# TinyMicroGameboy-smallbuttons.net
KiCad netlist of a schematic drawn in EAGLE
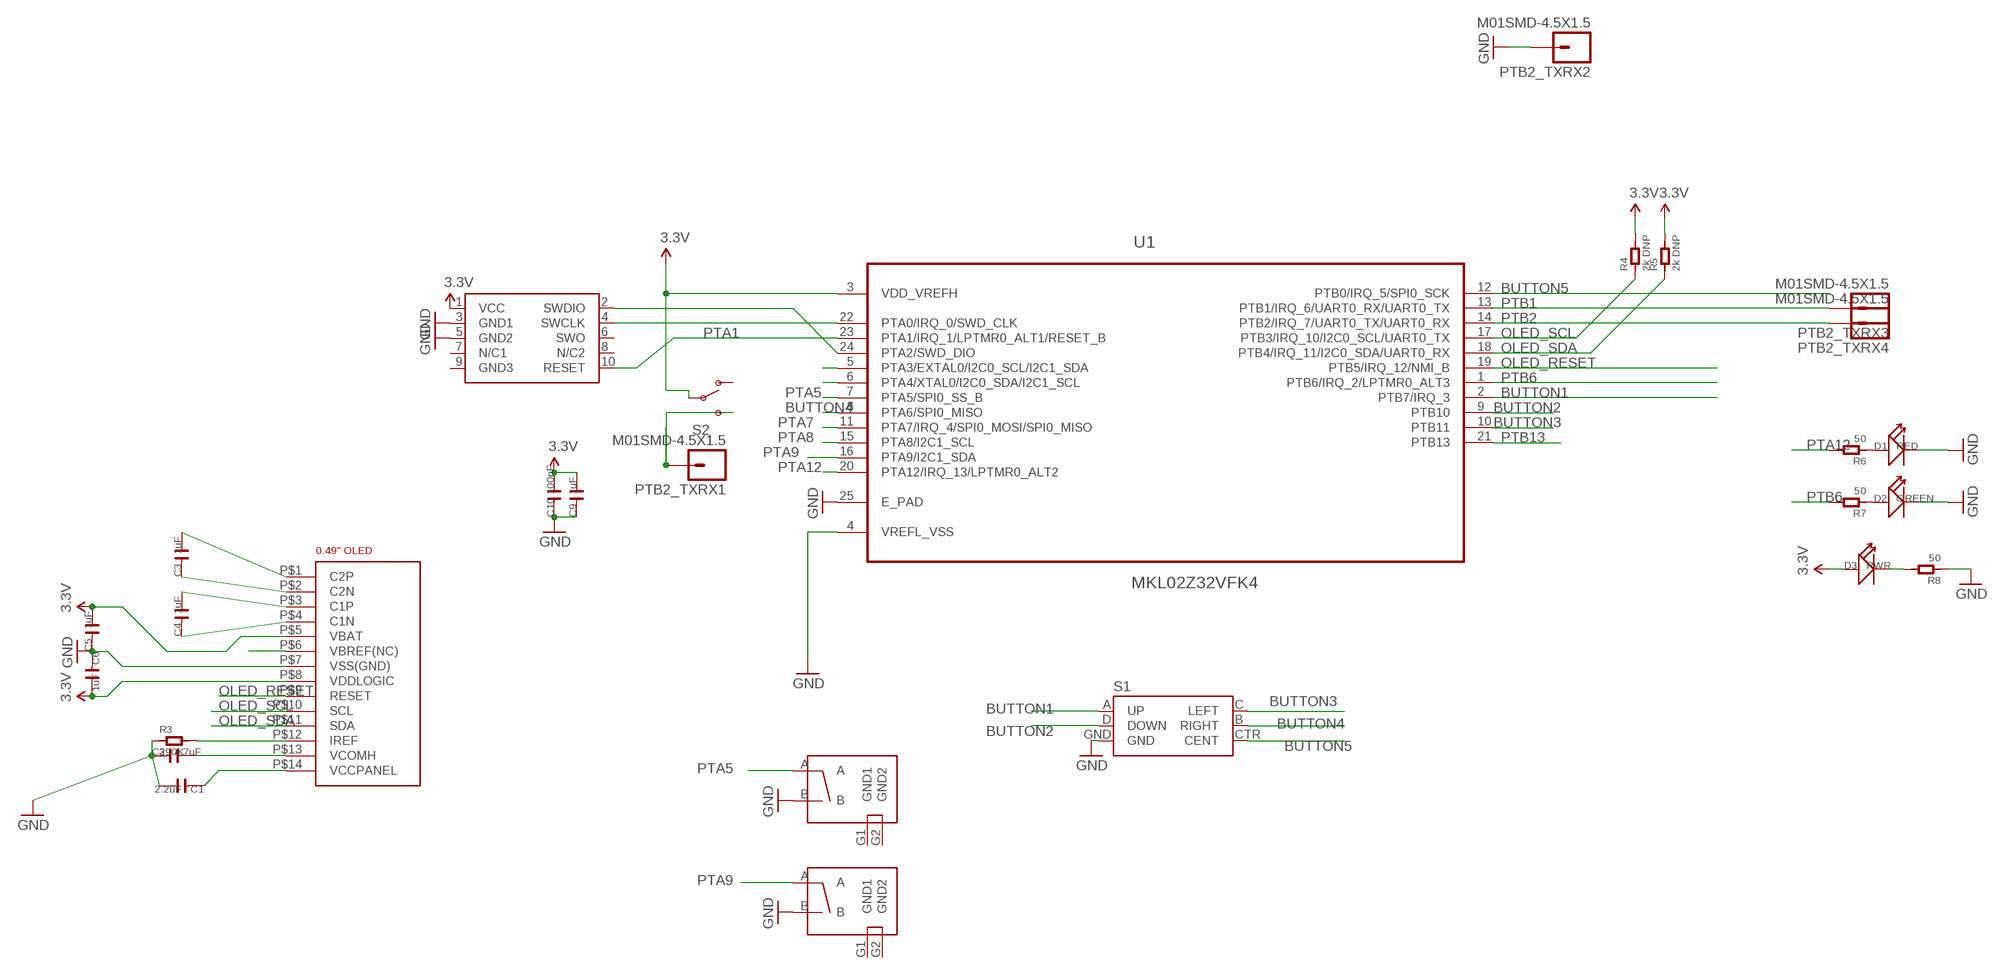
[diagram p0: schematic, sheet 1]

(export (version "E")
  (design (tool "Eeschema 10.0.6"))
  (components
    (comp (ref "C1")
      (value "2.2uF")
      (footprint "eagle-import:C0603")
      (libsource (lib "eagle-import") (part "C-0603"))
    )
    (comp (ref "C2")
      (value "4.7uF")
      (footprint "eagle-import:C0603")
      (libsource (lib "eagle-import") (part "C-0603"))
    )
    (comp (ref "C3")
      (value "1uF")
      (footprint "eagle-import:C0603")
      (libsource (lib "eagle-import") (part "C-0603"))
    )
    (comp (ref "C4")
      (value "1uF")
      (footprint "eagle-import:C0603")
      (libsource (lib "eagle-import") (part "C-0603"))
    )
    (comp (ref "C5")
      (value "1uF")
      (footprint "eagle-import:C0603")
      (libsource (lib "eagle-import") (part "C-0603"))
    )
    (comp (ref "C6")
      (value "1uF")
      (footprint "eagle-import:C0603")
      (libsource (lib "eagle-import") (part "C-0603"))
    )
    (comp (ref "C9")
      (value "1uF")
      (footprint "eagle-import:C0603")
      (libsource (lib "eagle-import") (part "C-0603"))
    )
    (comp (ref "C10")
      (value "100nF")
      (footprint "eagle-import:C0603")
      (libsource (lib "eagle-import") (part "C-0603"))
    )
    (comp (ref "D1")
      (value "RED")
      (footprint "eagle-import:LED0603")
      (libsource (lib "eagle-import") (part "LED"))
    )
    (comp (ref "D2")
      (value "GREEN")
      (footprint "eagle-import:LED0603")
      (libsource (lib "eagle-import") (part "LED"))
    )
    (comp (ref "D3")
      (value "PWR")
      (footprint "eagle-import:LED0603")
      (libsource (lib "eagle-import") (part "LED"))
    )
    (comp (ref "PTB2_TXRX1")
      (value "M01SMD-4.5X1.5")
      (footprint "eagle-import:PAD-1.5X4.5")
      (libsource (lib "eagle-import") (part "M01SMD-4.5X1.5"))
    )
    (comp (ref "PTB2_TXRX2")
      (value "M01SMD-4.5X1.5")
      (footprint "eagle-import:PAD-1.5X4.5")
      (libsource (lib "eagle-import") (part "M01SMD-4.5X1.5"))
    )
    (comp (ref "PTB2_TXRX3")
      (value "M01SMD-4.5X1.5")
      (footprint "eagle-import:PAD-1.5X4.5")
      (libsource (lib "eagle-import") (part "M01SMD-4.5X1.5"))
    )
    (comp (ref "PTB2_TXRX4")
      (value "M01SMD-4.5X1.5")
      (footprint "eagle-import:PAD-1.5X4.5")
      (libsource (lib "eagle-import") (part "M01SMD-4.5X1.5"))
    )
    (comp (ref "R3")
      (value "390K")
      (footprint "eagle-import:R0603")
      (libsource (lib "eagle-import") (part "R-0603"))
    )
    (comp (ref "R4")
      (value "2k DNP")
      (footprint "eagle-import:R0603")
      (libsource (lib "eagle-import") (part "R-0603"))
    )
    (comp (ref "R5")
      (value "2k DNP")
      (footprint "eagle-import:R0603")
      (libsource (lib "eagle-import") (part "R-0603"))
    )
    (comp (ref "R6")
      (value "50")
      (footprint "eagle-import:R0603")
      (libsource (lib "eagle-import") (part "R-0603"))
    )
    (comp (ref "R7")
      (value "50")
      (footprint "eagle-import:R0603")
      (libsource (lib "eagle-import") (part "R-0603"))
    )
    (comp (ref "R8")
      (value "50")
      (footprint "eagle-import:R0603")
      (libsource (lib "eagle-import") (part "R-0603"))
    )
    (comp (ref "S1")
      (value "JOYSTICK_MINI")
      (footprint "eagle-import:JOYSTICK_MINI")
      (libsource (lib "eagle-import") (part "JOYSTICK_MINI"))
    )
    (comp (ref "S2")
      (value "SWITCH-SPDT-SMD-A")
      (footprint "eagle-import:SWITCH-SPST-SMD-A")
      (libsource (lib "eagle-import") (part "SWITCH-SPDT-SMD-A"))
    )
    (comp (ref "SWD1")
      (value "CORTEX_SWD")
      (footprint "eagle-import:M50-3600542")
      (libsource (lib "eagle-import") (part "CORTEX_SWD"))
    )
    (comp (ref "U$1")
      (value "0.49\"OLEDFOLDED")
      (footprint "eagle-import:0.49_-FPC-0.7-14-FOLDED")
      (libsource (lib "eagle-import") (part "0.49{dblquote}OLEDFOLDED"))
    )
    (comp (ref "U$2")
      (value "2PSWITCH_SMT_SIDEMOUNT")
      (footprint "eagle-import:2X4TACT")
      (libsource (lib "eagle-import") (part "2PSWITCH_SMT_SIDEMOUNT"))
    )
    (comp (ref "U$3")
      (value "2PSWITCH_SMT_SIDEMOUNT")
      (footprint "eagle-import:2X4TACT")
      (libsource (lib "eagle-import") (part "2PSWITCH_SMT_SIDEMOUNT"))
    )
    (comp (ref "U1")
      (value "MKL02Z32VFK4")
      (footprint "eagle-import:QFN50P400X400X100-25N")
      (libsource (lib "eagle-import") (part "MKL02Z32VFK4"))
    )
  )
  (nets
    (net (code "1") (name "/BUTTON1") (class "Default")
      (node (ref "S1") (pin "A") (pinfunction "UP_A") (pintype "bidirectional"))
      (node (ref "U1") (pin "2") (pinfunction "PTB7/IRQ_3_2") (pintype "bidirectional"))
    )
    (net (code "2") (name "/BUTTON2") (class "Default")
      (node (ref "S1") (pin "D") (pinfunction "DOWN_D") (pintype "bidirectional"))
      (node (ref "U1") (pin "9") (pinfunction "PTB10_9") (pintype "bidirectional"))
    )
    (net (code "3") (name "/BUTTON3") (class "Default")
      (node (ref "S1") (pin "C") (pinfunction "LEFT_C") (pintype "bidirectional"))
      (node (ref "U1") (pin "10") (pinfunction "PTB11_10") (pintype "bidirectional"))
    )
    (net (code "4") (name "/BUTTON4") (class "Default")
      (node (ref "S1") (pin "B") (pinfunction "RIGHT_B") (pintype "bidirectional"))
      (node (ref "U1") (pin "8") (pinfunction "PTA6/SPI0_MISO_8") (pintype "bidirectional"))
    )
    (net (code "5") (name "/BUTTON5") (class "Default")
      (node (ref "S1") (pin "CTR") (pinfunction "CENT_CTR") (pintype "bidirectional"))
      (node (ref "U1") (pin "12") (pinfunction "PTB0/IRQ_5/SPI0_SCK_12") (pintype "bidirectional"))
    )
    (net (code "6") (name "/OLED_RESET") (class "Default")
      (node (ref "U$1") (pin "P$9") (pinfunction "RESET_P$9") (pintype "bidirectional"))
      (node (ref "U1") (pin "19") (pinfunction "PTB5/IRQ_12/NMI_B_19") (pintype "bidirectional"))
    )
    (net (code "7") (name "/OLED_SCL") (class "Default")
      (node (ref "R4") (pin "1") (pinfunction "1_1") (pintype "bidirectional"))
      (node (ref "U$1") (pin "P$10") (pinfunction "SCL_P$10") (pintype "bidirectional"))
      (node (ref "U1") (pin "17") (pinfunction "PTB3/IRQ_10/I2C0_SCL/UART0_TX_17") (pintype "bidirectional"))
    )
    (net (code "8") (name "/OLED_SDA") (class "Default")
      (node (ref "R5") (pin "1") (pinfunction "1_1") (pintype "bidirectional"))
      (node (ref "U$1") (pin "P$11") (pinfunction "SDA_P$11") (pintype "bidirectional"))
      (node (ref "U1") (pin "18") (pinfunction "PTB4/IRQ_11/I2C0_SDA/UART0_RX_18") (pintype "bidirectional"))
    )
    (net (code "9") (name "/PTA1") (class "Default")
      (node (ref "SWD1") (pin "10") (pinfunction "RESET_10") (pintype "bidirectional"))
      (node (ref "U1") (pin "23") (pinfunction "PTA1/IRQ_1/LPTMR0_ALT1/RESET_B_23") (pintype "bidirectional"))
    )
    (net (code "10") (name "/PTA5") (class "Default")
      (node (ref "U$2") (pin "A") (pinfunction "A_A") (pintype "bidirectional"))
      (node (ref "U1") (pin "7") (pinfunction "PTA5/SPI0_SS_B_7") (pintype "bidirectional"))
    )
    (net (code "11") (name "/PTA7") (class "Default")
      (node (ref "U1") (pin "11") (pinfunction "PTA7/IRQ_4/SPI0_MOSI/SPI0_MISO_11") (pintype "bidirectional"))
    )
    (net (code "12") (name "/PTA8") (class "Default")
      (node (ref "U1") (pin "15") (pinfunction "PTA8/I2C1_SCL_15") (pintype "bidirectional"))
    )
    (net (code "13") (name "/PTA9") (class "Default")
      (node (ref "U$3") (pin "A") (pinfunction "A_A") (pintype "bidirectional"))
      (node (ref "U1") (pin "16") (pinfunction "PTA9/I2C1_SDA_16") (pintype "bidirectional"))
    )
    (net (code "14") (name "/PTA12") (class "Default")
      (node (ref "R6") (pin "2") (pinfunction "2_2") (pintype "bidirectional"))
      (node (ref "U1") (pin "20") (pinfunction "PTA12/IRQ_13/LPTMR0_ALT2_20") (pintype "bidirectional"))
    )
    (net (code "15") (name "/PTB1") (class "Default")
      (node (ref "PTB2_TXRX3") (pin "P$1") (pinfunction "1_P$1") (pintype "passive"))
      (node (ref "U1") (pin "13") (pinfunction "PTB1/IRQ_6/UART0_RX/UART0_TX_13") (pintype "bidirectional"))
    )
    (net (code "16") (name "/PTB2") (class "Default")
      (node (ref "PTB2_TXRX4") (pin "P$1") (pinfunction "1_P$1") (pintype "passive"))
      (node (ref "U1") (pin "14") (pinfunction "PTB2/IRQ_7/UART0_TX/UART0_RX_14") (pintype "bidirectional"))
    )
    (net (code "17") (name "/PTB6") (class "Default")
      (node (ref "R7") (pin "2") (pinfunction "2_2") (pintype "bidirectional"))
      (node (ref "U1") (pin "1") (pinfunction "PTB6/IRQ_2/LPTMR0_ALT3_1") (pintype "bidirectional"))
    )
    (net (code "18") (name "/PTB13") (class "Default")
      (node (ref "U1") (pin "21") (pinfunction "PTB13_21") (pintype "bidirectional"))
    )
    (net (code "19") (name "3.3V") (class "Default")
      (node (ref "C10") (pin "2") (pinfunction "2_2") (pintype "bidirectional"))
      (node (ref "C5") (pin "2") (pinfunction "2_2") (pintype "bidirectional"))
      (node (ref "C6") (pin "2") (pinfunction "2_2") (pintype "bidirectional"))
      (node (ref "C9") (pin "2") (pinfunction "2_2") (pintype "bidirectional"))
      (node (ref "D3") (pin "+") (pinfunction "+_+") (pintype "passive"))
      (node (ref "R4") (pin "2") (pinfunction "2_2") (pintype "bidirectional"))
      (node (ref "R5") (pin "2") (pinfunction "2_2") (pintype "bidirectional"))
      (node (ref "S2") (pin "2") (pinfunction "P_2") (pintype "passive"))
      (node (ref "SWD1") (pin "1") (pinfunction "VCC_1") (pintype "bidirectional"))
      (node (ref "U$1") (pin "P$5") (pinfunction "VBAT_P$5") (pintype "bidirectional"))
      (node (ref "U$1") (pin "P$8") (pinfunction "VDDLOGIC_P$8") (pintype "bidirectional"))
      (node (ref "U1") (pin "3") (pinfunction "VDD_VREFH_3") (pintype "power_in"))
    )
    (net (code "20") (name "GND") (class "Default")
      (node (ref "C1") (pin "2") (pinfunction "2_2") (pintype "bidirectional"))
      (node (ref "C10") (pin "1") (pinfunction "1_1") (pintype "bidirectional"))
      (node (ref "C2") (pin "1") (pinfunction "1_1") (pintype "bidirectional"))
      (node (ref "C5") (pin "1") (pinfunction "1_1") (pintype "bidirectional"))
      (node (ref "C6") (pin "1") (pinfunction "1_1") (pintype "bidirectional"))
      (node (ref "C9") (pin "1") (pinfunction "1_1") (pintype "bidirectional"))
      (node (ref "D1") (pin "-") (pinfunction "-_-") (pintype "passive"))
      (node (ref "D2") (pin "-") (pinfunction "-_-") (pintype "passive"))
      (node (ref "PTB2_TXRX2") (pin "P$1") (pinfunction "1_P$1") (pintype "passive"))
      (node (ref "R3") (pin "1") (pinfunction "1_1") (pintype "bidirectional"))
      (node (ref "R8") (pin "1") (pinfunction "1_1") (pintype "bidirectional"))
      (node (ref "S1") (pin "GND") (pinfunction "GND_GND") (pintype "bidirectional"))
      (node (ref "SWD1") (pin "3") (pinfunction "GND1_3") (pintype "bidirectional"))
      (node (ref "SWD1") (pin "5") (pinfunction "GND2_5") (pintype "bidirectional"))
      (node (ref "U$1") (pin "P$7") (pinfunction "VSS(GND)_P$7") (pintype "bidirectional"))
      (node (ref "U$2") (pin "B") (pinfunction "B_B") (pintype "bidirectional"))
      (node (ref "U$3") (pin "B") (pinfunction "B_B") (pintype "bidirectional"))
      (node (ref "U1") (pin "25") (pinfunction "E_PAD_25") (pintype "passive"))
      (node (ref "U1") (pin "4") (pinfunction "VREFL_VSS_4") (pintype "passive"))
    )
    (net (code "21") (name "Net-(D1-Pad+)") (class "Default")
      (node (ref "D1") (pin "+") (pinfunction "+_+") (pintype "passive"))
      (node (ref "R6") (pin "1") (pinfunction "1_1") (pintype "bidirectional"))
    )
    (net (code "22") (name "Net-(D2-Pad+)") (class "Default")
      (node (ref "D2") (pin "+") (pinfunction "+_+") (pintype "passive"))
      (node (ref "R7") (pin "1") (pinfunction "1_1") (pintype "bidirectional"))
    )
    (net (code "23") (name "Net-(D3-Pad-)") (class "Default")
      (node (ref "D3") (pin "-") (pinfunction "-_-") (pintype "passive"))
      (node (ref "R8") (pin "2") (pinfunction "2_2") (pintype "bidirectional"))
    )
    (net (code "24") (name "Net-(PTB2_TXRX1-1)") (class "Default")
      (node (ref "PTB2_TXRX1") (pin "P$1") (pinfunction "1_P$1") (pintype "passive"))
      (node (ref "S2") (pin "3") (pinfunction "S_3") (pintype "passive"))
    )
    (net (code "25") (name "Net-(SWD1-SWCLK)") (class "Default")
      (node (ref "SWD1") (pin "4") (pinfunction "SWCLK_4") (pintype "bidirectional"))
      (node (ref "U1") (pin "22") (pinfunction "PTA0/IRQ_0/SWD_CLK_22") (pintype "bidirectional"))
    )
    (net (code "26") (name "Net-(SWD1-SWDIO)") (class "Default")
      (node (ref "SWD1") (pin "2") (pinfunction "SWDIO_2") (pintype "bidirectional"))
      (node (ref "U1") (pin "24") (pinfunction "PTA2/SWD_DIO_24") (pintype "bidirectional"))
    )
    (net (code "27") (name "Net-(U$1-C1N)") (class "Default")
      (node (ref "C4") (pin "1") (pinfunction "1_1") (pintype "bidirectional"))
      (node (ref "U$1") (pin "P$4") (pinfunction "C1N_P$4") (pintype "bidirectional"))
    )
    (net (code "28") (name "Net-(U$1-C1P)") (class "Default")
      (node (ref "C4") (pin "2") (pinfunction "2_2") (pintype "bidirectional"))
      (node (ref "U$1") (pin "P$3") (pinfunction "C1P_P$3") (pintype "bidirectional"))
    )
    (net (code "29") (name "Net-(U$1-C2N)") (class "Default")
      (node (ref "C3") (pin "1") (pinfunction "1_1") (pintype "bidirectional"))
      (node (ref "U$1") (pin "P$2") (pinfunction "C2N_P$2") (pintype "bidirectional"))
    )
    (net (code "30") (name "Net-(U$1-C2P)") (class "Default")
      (node (ref "C3") (pin "2") (pinfunction "2_2") (pintype "bidirectional"))
      (node (ref "U$1") (pin "P$1") (pinfunction "C2P_P$1") (pintype "bidirectional"))
    )
    (net (code "31") (name "Net-(U$1-IREF)") (class "Default")
      (node (ref "R3") (pin "2") (pinfunction "2_2") (pintype "bidirectional"))
      (node (ref "U$1") (pin "P$12") (pinfunction "IREF_P$12") (pintype "bidirectional"))
    )
    (net (code "32") (name "Net-(U$1-VCCPANEL)") (class "Default")
      (node (ref "C1") (pin "1") (pinfunction "1_1") (pintype "bidirectional"))
      (node (ref "U$1") (pin "P$14") (pinfunction "VCCPANEL_P$14") (pintype "bidirectional"))
    )
    (net (code "33") (name "Net-(U$1-VCOMH)") (class "Default")
      (node (ref "C2") (pin "2") (pinfunction "2_2") (pintype "bidirectional"))
      (node (ref "U$1") (pin "P$13") (pinfunction "VCOMH_P$13") (pintype "bidirectional"))
    )
    (net (code "34") (name "unconnected-(S2-O-Pad1)") (class "Default")
      (node (ref "S2") (pin "1") (pinfunction "O_1") (pintype "passive"))
    )
    (net (code "35") (name "unconnected-(SWD1-GND3-Pad9)") (class "Default")
      (node (ref "SWD1") (pin "9") (pinfunction "GND3_9") (pintype "bidirectional"))
    )
    (net (code "36") (name "unconnected-(SWD1-N{slash}C1-Pad7)") (class "Default")
      (node (ref "SWD1") (pin "7") (pinfunction "N/C1_7") (pintype "bidirectional"))
    )
    (net (code "37") (name "unconnected-(SWD1-N{slash}C2-Pad8)") (class "Default")
      (node (ref "SWD1") (pin "8") (pinfunction "N/C2_8") (pintype "bidirectional"))
    )
    (net (code "38") (name "unconnected-(SWD1-SWO-Pad6)") (class "Default")
      (node (ref "SWD1") (pin "6") (pinfunction "SWO_6") (pintype "bidirectional"))
    )
    (net (code "39") (name "unconnected-(U$1-VBREF(NC)-PadP$6)") (class "Default")
      (node (ref "U$1") (pin "P$6") (pinfunction "VBREF(NC)_P$6") (pintype "bidirectional"))
    )
    (net (code "40") (name "unconnected-(U$2-GND1-PadG1)") (class "Default")
      (node (ref "U$2") (pin "G1") (pinfunction "GND1_G1") (pintype "bidirectional"))
    )
    (net (code "41") (name "unconnected-(U$2-GND2-PadG2)") (class "Default")
      (node (ref "U$2") (pin "G2") (pinfunction "GND2_G2") (pintype "bidirectional"))
    )
    (net (code "42") (name "unconnected-(U$3-GND1-PadG1)") (class "Default")
      (node (ref "U$3") (pin "G1") (pinfunction "GND1_G1") (pintype "bidirectional"))
    )
    (net (code "43") (name "unconnected-(U$3-GND2-PadG2)") (class "Default")
      (node (ref "U$3") (pin "G2") (pinfunction "GND2_G2") (pintype "bidirectional"))
    )
    (net (code "44") (name "unconnected-(U1-PTA3{slash}EXTAL0{slash}I2C0_SCL{slash}I2C1_SDA-Pad5)") (class "Default")
      (node (ref "U1") (pin "5") (pinfunction "PTA3/EXTAL0/I2C0_SCL/I2C1_SDA_5") (pintype "bidirectional"))
    )
    (net (code "45") (name "unconnected-(U1-PTA4{slash}XTAL0{slash}I2C0_SDA{slash}I2C1_SCL-Pad6)") (class "Default")
      (node (ref "U1") (pin "6") (pinfunction "PTA4/XTAL0/I2C0_SDA/I2C1_SCL_6") (pintype "bidirectional"))
    )
  )
)
